# DIDV_-_Baixa_Latencia_Conex_o_Servos.net
KiCad netlist of a schematic drawn in EAGLE
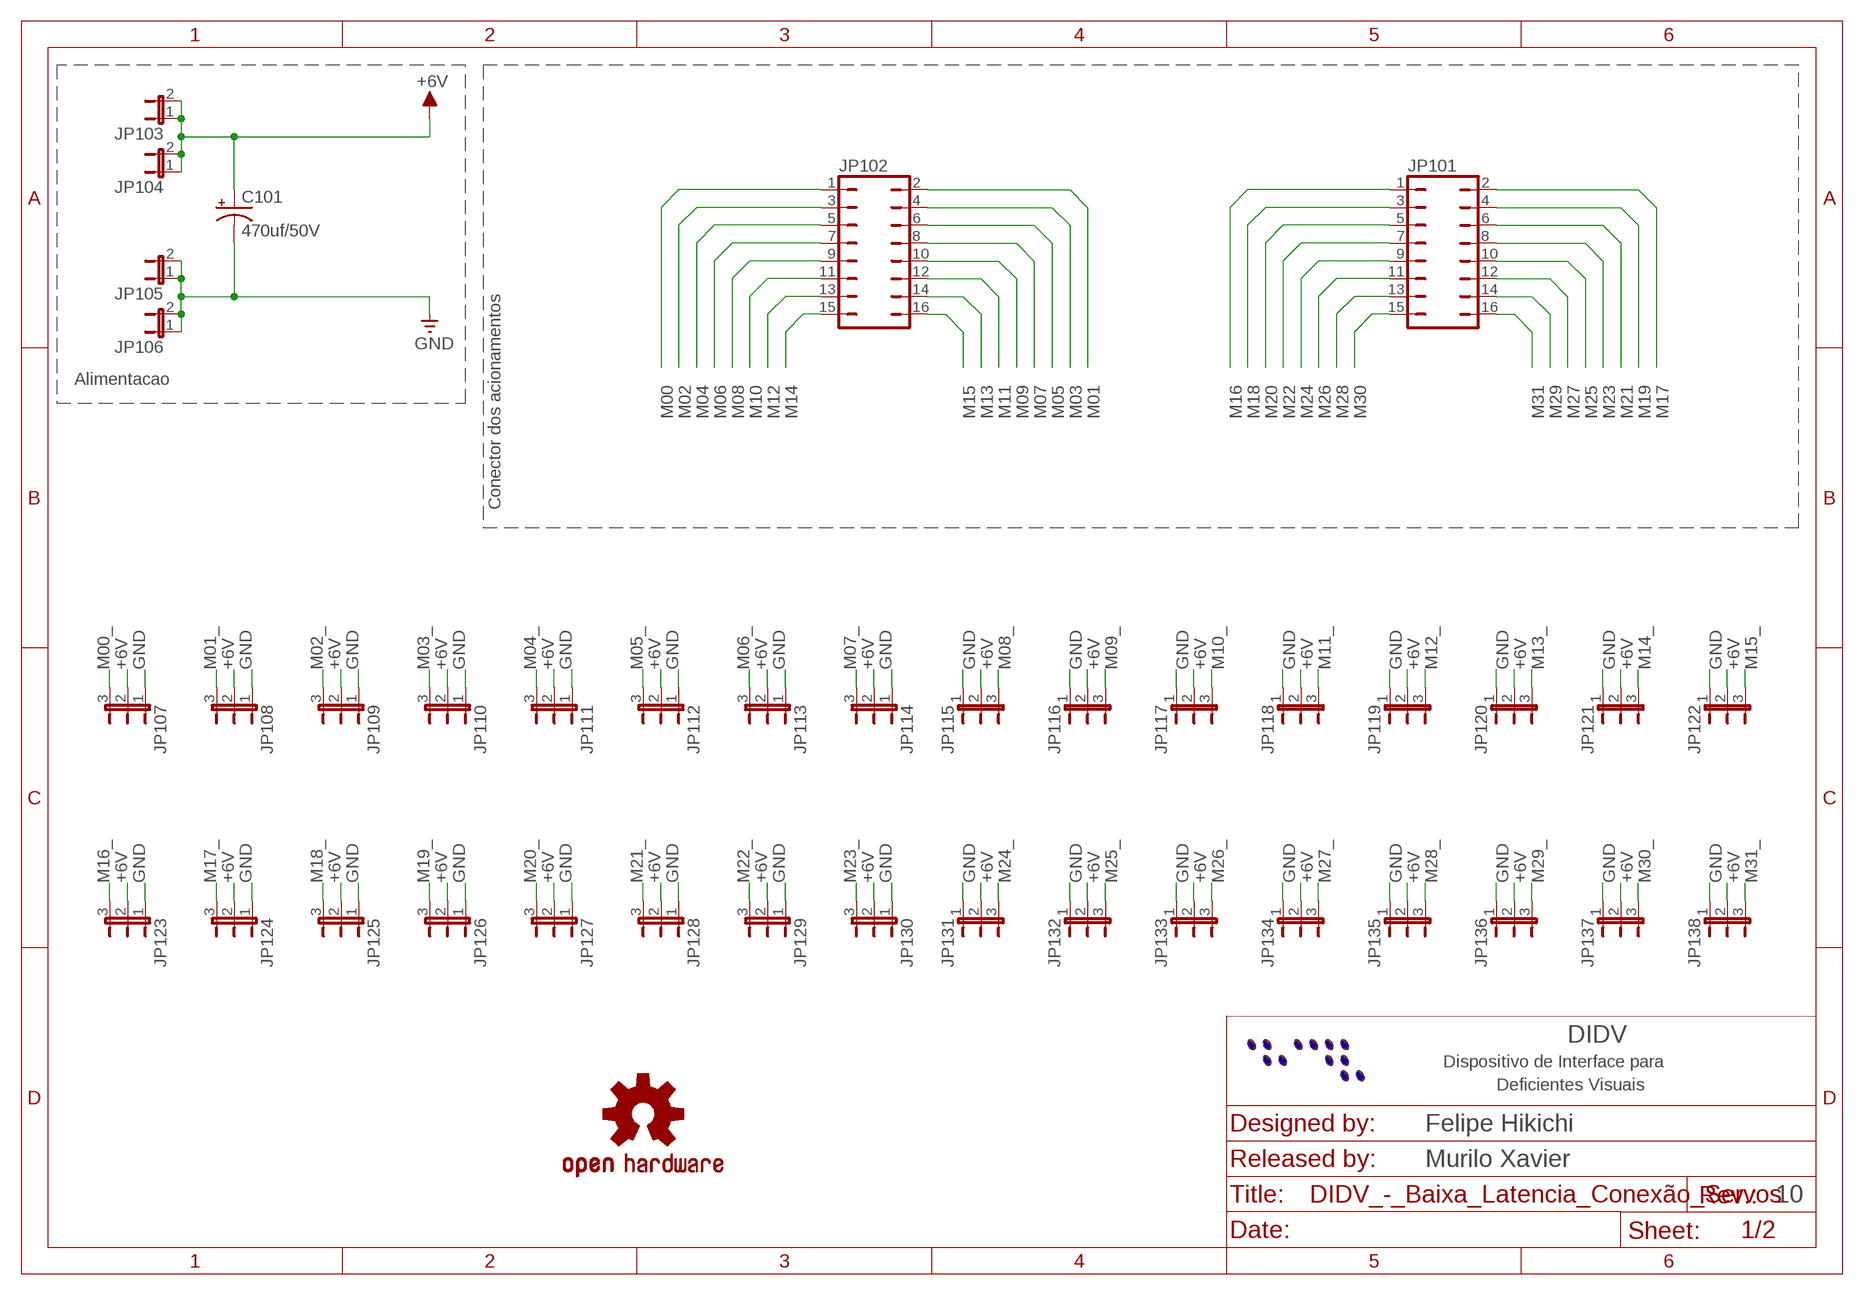
[diagram p0: schematic, sheet 1]
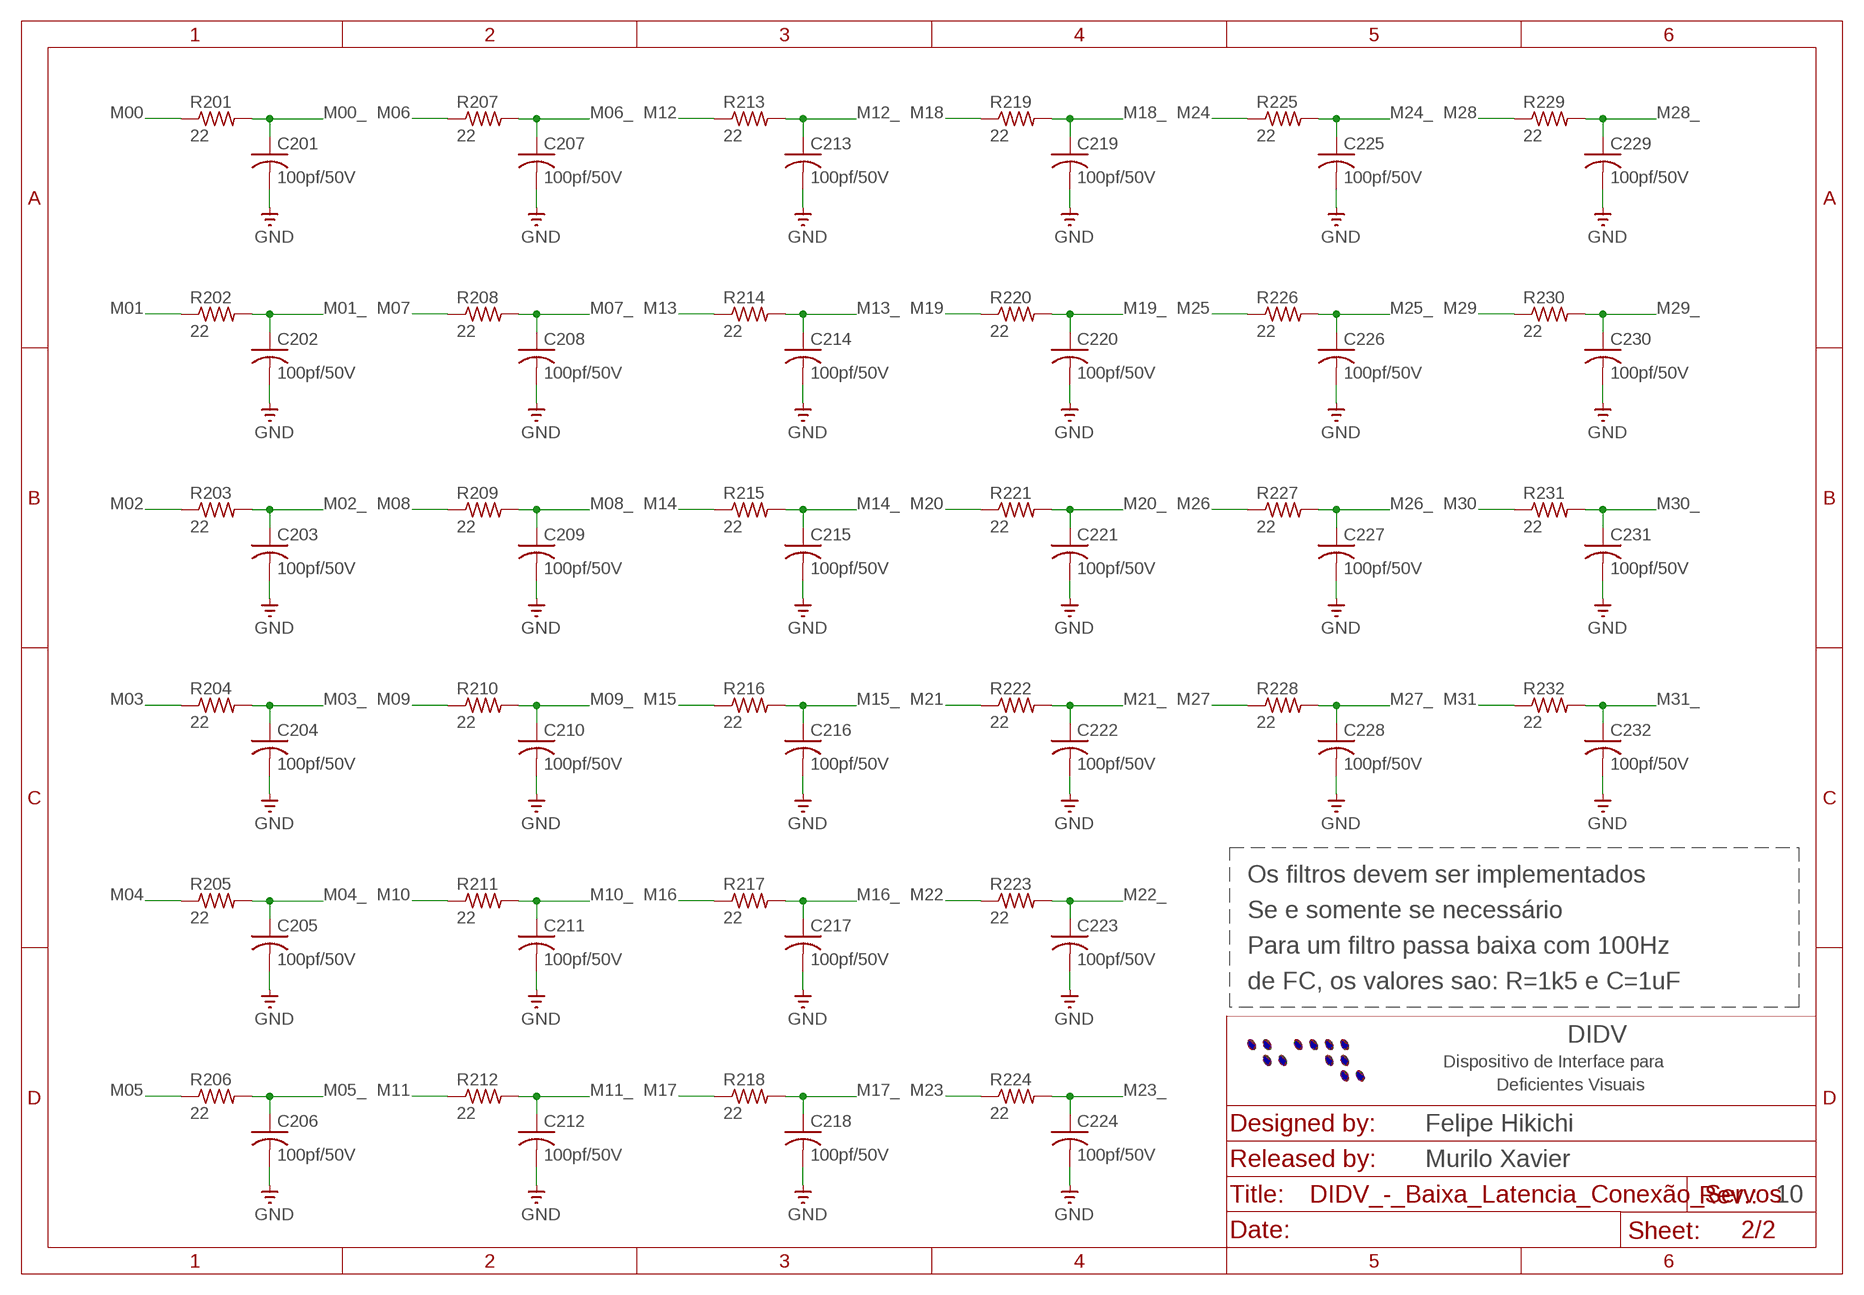
[diagram p1: schematic, sheet 2]

(export (version "E")
  (design (tool "Eeschema 10.0.6"))
  (components
    (comp (ref "C101")
      (value "470uf/50V")
      (footprint "eagle-import:140CLH-1010")
      (libsource (lib "eagle-import") (part "CPOL-US140CLH-1010"))
    )
    (comp (ref "JP101")
      (value "JP8Q")
      (footprint "eagle-import:JP8Q")
      (libsource (lib "eagle-import") (part "JP8Q"))
    )
    (comp (ref "JP102")
      (value "JP8Q")
      (footprint "eagle-import:JP8Q")
      (libsource (lib "eagle-import") (part "JP8Q"))
    )
    (comp (ref "JP103")
      (value "JP1E")
      (footprint "eagle-import:JP1")
      (libsource (lib "eagle-import") (part "JP1E"))
    )
    (comp (ref "JP104")
      (value "JP1E")
      (footprint "eagle-import:JP1")
      (libsource (lib "eagle-import") (part "JP1E"))
    )
    (comp (ref "JP105")
      (value "JP1E")
      (footprint "eagle-import:JP1")
      (libsource (lib "eagle-import") (part "JP1E"))
    )
    (comp (ref "JP106")
      (value "JP1E")
      (footprint "eagle-import:JP1")
      (libsource (lib "eagle-import") (part "JP1E"))
    )
    (comp (ref "JP107")
      (value "JP2E")
      (footprint "eagle-import:JP2")
      (libsource (lib "eagle-import") (part "JP2E"))
    )
    (comp (ref "JP108")
      (value "JP2E")
      (footprint "eagle-import:JP2")
      (libsource (lib "eagle-import") (part "JP2E"))
    )
    (comp (ref "JP109")
      (value "JP2E")
      (footprint "eagle-import:JP2")
      (libsource (lib "eagle-import") (part "JP2E"))
    )
    (comp (ref "JP110")
      (value "JP2E")
      (footprint "eagle-import:JP2")
      (libsource (lib "eagle-import") (part "JP2E"))
    )
    (comp (ref "JP111")
      (value "JP2E")
      (footprint "eagle-import:JP2")
      (libsource (lib "eagle-import") (part "JP2E"))
    )
    (comp (ref "JP112")
      (value "JP2E")
      (footprint "eagle-import:JP2")
      (libsource (lib "eagle-import") (part "JP2E"))
    )
    (comp (ref "JP113")
      (value "JP2E")
      (footprint "eagle-import:JP2")
      (libsource (lib "eagle-import") (part "JP2E"))
    )
    (comp (ref "JP114")
      (value "JP2E")
      (footprint "eagle-import:JP2")
      (libsource (lib "eagle-import") (part "JP2E"))
    )
    (comp (ref "JP115")
      (value "JP2E")
      (footprint "eagle-import:JP2")
      (libsource (lib "eagle-import") (part "JP2E"))
    )
    (comp (ref "JP116")
      (value "JP2E")
      (footprint "eagle-import:JP2")
      (libsource (lib "eagle-import") (part "JP2E"))
    )
    (comp (ref "JP117")
      (value "JP2E")
      (footprint "eagle-import:JP2")
      (libsource (lib "eagle-import") (part "JP2E"))
    )
    (comp (ref "JP118")
      (value "JP2E")
      (footprint "eagle-import:JP2")
      (libsource (lib "eagle-import") (part "JP2E"))
    )
    (comp (ref "JP119")
      (value "JP2E")
      (footprint "eagle-import:JP2")
      (libsource (lib "eagle-import") (part "JP2E"))
    )
    (comp (ref "JP120")
      (value "JP2E")
      (footprint "eagle-import:JP2")
      (libsource (lib "eagle-import") (part "JP2E"))
    )
    (comp (ref "JP121")
      (value "JP2E")
      (footprint "eagle-import:JP2")
      (libsource (lib "eagle-import") (part "JP2E"))
    )
    (comp (ref "JP122")
      (value "JP2E")
      (footprint "eagle-import:JP2")
      (libsource (lib "eagle-import") (part "JP2E"))
    )
    (comp (ref "JP123")
      (value "JP2E")
      (footprint "eagle-import:JP2")
      (libsource (lib "eagle-import") (part "JP2E"))
    )
    (comp (ref "JP124")
      (value "JP2E")
      (footprint "eagle-import:JP2")
      (libsource (lib "eagle-import") (part "JP2E"))
    )
    (comp (ref "JP125")
      (value "JP2E")
      (footprint "eagle-import:JP2")
      (libsource (lib "eagle-import") (part "JP2E"))
    )
    (comp (ref "JP126")
      (value "JP2E")
      (footprint "eagle-import:JP2")
      (libsource (lib "eagle-import") (part "JP2E"))
    )
    (comp (ref "JP127")
      (value "JP2E")
      (footprint "eagle-import:JP2")
      (libsource (lib "eagle-import") (part "JP2E"))
    )
    (comp (ref "JP128")
      (value "JP2E")
      (footprint "eagle-import:JP2")
      (libsource (lib "eagle-import") (part "JP2E"))
    )
    (comp (ref "JP129")
      (value "JP2E")
      (footprint "eagle-import:JP2")
      (libsource (lib "eagle-import") (part "JP2E"))
    )
    (comp (ref "JP130")
      (value "JP2E")
      (footprint "eagle-import:JP2")
      (libsource (lib "eagle-import") (part "JP2E"))
    )
    (comp (ref "JP131")
      (value "JP2E")
      (footprint "eagle-import:JP2")
      (libsource (lib "eagle-import") (part "JP2E"))
    )
    (comp (ref "JP132")
      (value "JP2E")
      (footprint "eagle-import:JP2")
      (libsource (lib "eagle-import") (part "JP2E"))
    )
    (comp (ref "JP133")
      (value "JP2E")
      (footprint "eagle-import:JP2")
      (libsource (lib "eagle-import") (part "JP2E"))
    )
    (comp (ref "JP134")
      (value "JP2E")
      (footprint "eagle-import:JP2")
      (libsource (lib "eagle-import") (part "JP2E"))
    )
    (comp (ref "JP135")
      (value "JP2E")
      (footprint "eagle-import:JP2")
      (libsource (lib "eagle-import") (part "JP2E"))
    )
    (comp (ref "JP136")
      (value "JP2E")
      (footprint "eagle-import:JP2")
      (libsource (lib "eagle-import") (part "JP2E"))
    )
    (comp (ref "JP137")
      (value "JP2E")
      (footprint "eagle-import:JP2")
      (libsource (lib "eagle-import") (part "JP2E"))
    )
    (comp (ref "JP138")
      (value "JP2E")
      (footprint "eagle-import:JP2")
      (libsource (lib "eagle-import") (part "JP2E"))
    )
    (comp (ref "LOGO101")
      (value "OSHW-LOGOL")
      (footprint "eagle-import:OSHW-LOGO-L")
      (libsource (lib "eagle-import") (part "OSHW-LOGOL"))
    )
    (comp (ref "C201")
      (value "100pf/50V")
      (footprint "eagle-import:C0603")
      (libsource (lib "eagle-import") (part "C-USC0603"))
    )
    (comp (ref "C202")
      (value "100pf/50V")
      (footprint "eagle-import:C0603")
      (libsource (lib "eagle-import") (part "C-USC0603"))
    )
    (comp (ref "C203")
      (value "100pf/50V")
      (footprint "eagle-import:C0603")
      (libsource (lib "eagle-import") (part "C-USC0603"))
    )
    (comp (ref "C204")
      (value "100pf/50V")
      (footprint "eagle-import:C0603")
      (libsource (lib "eagle-import") (part "C-USC0603"))
    )
    (comp (ref "C205")
      (value "100pf/50V")
      (footprint "eagle-import:C0603")
      (libsource (lib "eagle-import") (part "C-USC0603"))
    )
    (comp (ref "C206")
      (value "100pf/50V")
      (footprint "eagle-import:C0603")
      (libsource (lib "eagle-import") (part "C-USC0603"))
    )
    (comp (ref "C207")
      (value "100pf/50V")
      (footprint "eagle-import:C0603")
      (libsource (lib "eagle-import") (part "C-USC0603"))
    )
    (comp (ref "C208")
      (value "100pf/50V")
      (footprint "eagle-import:C0603")
      (libsource (lib "eagle-import") (part "C-USC0603"))
    )
    (comp (ref "C209")
      (value "100pf/50V")
      (footprint "eagle-import:C0603")
      (libsource (lib "eagle-import") (part "C-USC0603"))
    )
    (comp (ref "C210")
      (value "100pf/50V")
      (footprint "eagle-import:C0603")
      (libsource (lib "eagle-import") (part "C-USC0603"))
    )
    (comp (ref "C211")
      (value "100pf/50V")
      (footprint "eagle-import:C0603")
      (libsource (lib "eagle-import") (part "C-USC0603"))
    )
    (comp (ref "C212")
      (value "100pf/50V")
      (footprint "eagle-import:C0603")
      (libsource (lib "eagle-import") (part "C-USC0603"))
    )
    (comp (ref "C213")
      (value "100pf/50V")
      (footprint "eagle-import:C0603")
      (libsource (lib "eagle-import") (part "C-USC0603"))
    )
    (comp (ref "C214")
      (value "100pf/50V")
      (footprint "eagle-import:C0603")
      (libsource (lib "eagle-import") (part "C-USC0603"))
    )
    (comp (ref "C215")
      (value "100pf/50V")
      (footprint "eagle-import:C0603")
      (libsource (lib "eagle-import") (part "C-USC0603"))
    )
    (comp (ref "C216")
      (value "100pf/50V")
      (footprint "eagle-import:C0603")
      (libsource (lib "eagle-import") (part "C-USC0603"))
    )
    (comp (ref "C217")
      (value "100pf/50V")
      (footprint "eagle-import:C0603")
      (libsource (lib "eagle-import") (part "C-USC0603"))
    )
    (comp (ref "C218")
      (value "100pf/50V")
      (footprint "eagle-import:C0603")
      (libsource (lib "eagle-import") (part "C-USC0603"))
    )
    (comp (ref "C219")
      (value "100pf/50V")
      (footprint "eagle-import:C0603")
      (libsource (lib "eagle-import") (part "C-USC0603"))
    )
    (comp (ref "C220")
      (value "100pf/50V")
      (footprint "eagle-import:C0603")
      (libsource (lib "eagle-import") (part "C-USC0603"))
    )
    (comp (ref "C221")
      (value "100pf/50V")
      (footprint "eagle-import:C0603")
      (libsource (lib "eagle-import") (part "C-USC0603"))
    )
    (comp (ref "C222")
      (value "100pf/50V")
      (footprint "eagle-import:C0603")
      (libsource (lib "eagle-import") (part "C-USC0603"))
    )
    (comp (ref "C223")
      (value "100pf/50V")
      (footprint "eagle-import:C0603")
      (libsource (lib "eagle-import") (part "C-USC0603"))
    )
    (comp (ref "C224")
      (value "100pf/50V")
      (footprint "eagle-import:C0603")
      (libsource (lib "eagle-import") (part "C-USC0603"))
    )
    (comp (ref "C225")
      (value "100pf/50V")
      (footprint "eagle-import:C0603")
      (libsource (lib "eagle-import") (part "C-USC0603"))
    )
    (comp (ref "C226")
      (value "100pf/50V")
      (footprint "eagle-import:C0603")
      (libsource (lib "eagle-import") (part "C-USC0603"))
    )
    (comp (ref "C227")
      (value "100pf/50V")
      (footprint "eagle-import:C0603")
      (libsource (lib "eagle-import") (part "C-USC0603"))
    )
    (comp (ref "C228")
      (value "100pf/50V")
      (footprint "eagle-import:C0603")
      (libsource (lib "eagle-import") (part "C-USC0603"))
    )
    (comp (ref "C229")
      (value "100pf/50V")
      (footprint "eagle-import:C0603")
      (libsource (lib "eagle-import") (part "C-USC0603"))
    )
    (comp (ref "C230")
      (value "100pf/50V")
      (footprint "eagle-import:C0603")
      (libsource (lib "eagle-import") (part "C-USC0603"))
    )
    (comp (ref "C231")
      (value "100pf/50V")
      (footprint "eagle-import:C0603")
      (libsource (lib "eagle-import") (part "C-USC0603"))
    )
    (comp (ref "C232")
      (value "100pf/50V")
      (footprint "eagle-import:C0603")
      (libsource (lib "eagle-import") (part "C-USC0603"))
    )
    (comp (ref "R201")
      (value "22")
      (footprint "eagle-import:R0603")
      (libsource (lib "eagle-import") (part "R-US_R0603"))
    )
    (comp (ref "R202")
      (value "22")
      (footprint "eagle-import:R0603")
      (libsource (lib "eagle-import") (part "R-US_R0603"))
    )
    (comp (ref "R203")
      (value "22")
      (footprint "eagle-import:R0603")
      (libsource (lib "eagle-import") (part "R-US_R0603"))
    )
    (comp (ref "R204")
      (value "22")
      (footprint "eagle-import:R0603")
      (libsource (lib "eagle-import") (part "R-US_R0603"))
    )
    (comp (ref "R205")
      (value "22")
      (footprint "eagle-import:R0603")
      (libsource (lib "eagle-import") (part "R-US_R0603"))
    )
    (comp (ref "R206")
      (value "22")
      (footprint "eagle-import:R0603")
      (libsource (lib "eagle-import") (part "R-US_R0603"))
    )
    (comp (ref "R207")
      (value "22")
      (footprint "eagle-import:R0603")
      (libsource (lib "eagle-import") (part "R-US_R0603"))
    )
    (comp (ref "R208")
      (value "22")
      (footprint "eagle-import:R0603")
      (libsource (lib "eagle-import") (part "R-US_R0603"))
    )
    (comp (ref "R209")
      (value "22")
      (footprint "eagle-import:R0603")
      (libsource (lib "eagle-import") (part "R-US_R0603"))
    )
    (comp (ref "R210")
      (value "22")
      (footprint "eagle-import:R0603")
      (libsource (lib "eagle-import") (part "R-US_R0603"))
    )
    (comp (ref "R211")
      (value "22")
      (footprint "eagle-import:R0603")
      (libsource (lib "eagle-import") (part "R-US_R0603"))
    )
    (comp (ref "R212")
      (value "22")
      (footprint "eagle-import:R0603")
      (libsource (lib "eagle-import") (part "R-US_R0603"))
    )
    (comp (ref "R213")
      (value "22")
      (footprint "eagle-import:R0603")
      (libsource (lib "eagle-import") (part "R-US_R0603"))
    )
    (comp (ref "R214")
      (value "22")
      (footprint "eagle-import:R0603")
      (libsource (lib "eagle-import") (part "R-US_R0603"))
    )
    (comp (ref "R215")
      (value "22")
      (footprint "eagle-import:R0603")
      (libsource (lib "eagle-import") (part "R-US_R0603"))
    )
    (comp (ref "R216")
      (value "22")
      (footprint "eagle-import:R0603")
      (libsource (lib "eagle-import") (part "R-US_R0603"))
    )
    (comp (ref "R217")
      (value "22")
      (footprint "eagle-import:R0603")
      (libsource (lib "eagle-import") (part "R-US_R0603"))
    )
    (comp (ref "R218")
      (value "22")
      (footprint "eagle-import:R0603")
      (libsource (lib "eagle-import") (part "R-US_R0603"))
    )
    (comp (ref "R219")
      (value "22")
      (footprint "eagle-import:R0603")
      (libsource (lib "eagle-import") (part "R-US_R0603"))
    )
    (comp (ref "R220")
      (value "22")
      (footprint "eagle-import:R0603")
      (libsource (lib "eagle-import") (part "R-US_R0603"))
    )
    (comp (ref "R221")
      (value "22")
      (footprint "eagle-import:R0603")
      (libsource (lib "eagle-import") (part "R-US_R0603"))
    )
    (comp (ref "R222")
      (value "22")
      (footprint "eagle-import:R0603")
      (libsource (lib "eagle-import") (part "R-US_R0603"))
    )
    (comp (ref "R223")
      (value "22")
      (footprint "eagle-import:R0603")
      (libsource (lib "eagle-import") (part "R-US_R0603"))
    )
    (comp (ref "R224")
      (value "22")
      (footprint "eagle-import:R0603")
      (libsource (lib "eagle-import") (part "R-US_R0603"))
    )
    (comp (ref "R225")
      (value "22")
      (footprint "eagle-import:R0603")
      (libsource (lib "eagle-import") (part "R-US_R0603"))
    )
    (comp (ref "R226")
      (value "22")
      (footprint "eagle-import:R0603")
      (libsource (lib "eagle-import") (part "R-US_R0603"))
    )
    (comp (ref "R227")
      (value "22")
      (footprint "eagle-import:R0603")
      (libsource (lib "eagle-import") (part "R-US_R0603"))
    )
    (comp (ref "R228")
      (value "22")
      (footprint "eagle-import:R0603")
      (libsource (lib "eagle-import") (part "R-US_R0603"))
    )
    (comp (ref "R229")
      (value "22")
      (footprint "eagle-import:R0603")
      (libsource (lib "eagle-import") (part "R-US_R0603"))
    )
    (comp (ref "R230")
      (value "22")
      (footprint "eagle-import:R0603")
      (libsource (lib "eagle-import") (part "R-US_R0603"))
    )
    (comp (ref "R231")
      (value "22")
      (footprint "eagle-import:R0603")
      (libsource (lib "eagle-import") (part "R-US_R0603"))
    )
    (comp (ref "R232")
      (value "22")
      (footprint "eagle-import:R0603")
      (libsource (lib "eagle-import") (part "R-US_R0603"))
    )
  )
  (nets
    (net (code "1") (name "+6V") (class "Default")
      (node (ref "C101") (pin "+") (pinfunction "+_+") (pintype "passive"))
      (node (ref "JP103") (pin "1") (pinfunction "1_1") (pintype "passive"))
      (node (ref "JP103") (pin "2") (pinfunction "2_2") (pintype "passive"))
      (node (ref "JP104") (pin "1") (pinfunction "1_1") (pintype "passive"))
      (node (ref "JP104") (pin "2") (pinfunction "2_2") (pintype "passive"))
      (node (ref "JP107") (pin "2") (pinfunction "2_2") (pintype "passive"))
      (node (ref "JP108") (pin "2") (pinfunction "2_2") (pintype "passive"))
      (node (ref "JP109") (pin "2") (pinfunction "2_2") (pintype "passive"))
      (node (ref "JP110") (pin "2") (pinfunction "2_2") (pintype "passive"))
      (node (ref "JP111") (pin "2") (pinfunction "2_2") (pintype "passive"))
      (node (ref "JP112") (pin "2") (pinfunction "2_2") (pintype "passive"))
      (node (ref "JP113") (pin "2") (pinfunction "2_2") (pintype "passive"))
      (node (ref "JP114") (pin "2") (pinfunction "2_2") (pintype "passive"))
      (node (ref "JP115") (pin "2") (pinfunction "2_2") (pintype "passive"))
      (node (ref "JP116") (pin "2") (pinfunction "2_2") (pintype "passive"))
      (node (ref "JP117") (pin "2") (pinfunction "2_2") (pintype "passive"))
      (node (ref "JP118") (pin "2") (pinfunction "2_2") (pintype "passive"))
      (node (ref "JP119") (pin "2") (pinfunction "2_2") (pintype "passive"))
      (node (ref "JP120") (pin "2") (pinfunction "2_2") (pintype "passive"))
      (node (ref "JP121") (pin "2") (pinfunction "2_2") (pintype "passive"))
      (node (ref "JP122") (pin "2") (pinfunction "2_2") (pintype "passive"))
      (node (ref "JP123") (pin "2") (pinfunction "2_2") (pintype "passive"))
      (node (ref "JP124") (pin "2") (pinfunction "2_2") (pintype "passive"))
      (node (ref "JP125") (pin "2") (pinfunction "2_2") (pintype "passive"))
      (node (ref "JP126") (pin "2") (pinfunction "2_2") (pintype "passive"))
      (node (ref "JP127") (pin "2") (pinfunction "2_2") (pintype "passive"))
      (node (ref "JP128") (pin "2") (pinfunction "2_2") (pintype "passive"))
      (node (ref "JP129") (pin "2") (pinfunction "2_2") (pintype "passive"))
      (node (ref "JP130") (pin "2") (pinfunction "2_2") (pintype "passive"))
      (node (ref "JP131") (pin "2") (pinfunction "2_2") (pintype "passive"))
      (node (ref "JP132") (pin "2") (pinfunction "2_2") (pintype "passive"))
      (node (ref "JP133") (pin "2") (pinfunction "2_2") (pintype "passive"))
      (node (ref "JP134") (pin "2") (pinfunction "2_2") (pintype "passive"))
      (node (ref "JP135") (pin "2") (pinfunction "2_2") (pintype "passive"))
      (node (ref "JP136") (pin "2") (pinfunction "2_2") (pintype "passive"))
      (node (ref "JP137") (pin "2") (pinfunction "2_2") (pintype "passive"))
      (node (ref "JP138") (pin "2") (pinfunction "2_2") (pintype "passive"))
    )
    (net (code "2") (name "GND") (class "Default")
      (node (ref "C101") (pin "-") (pinfunction "-_-") (pintype "passive"))
      (node (ref "C201") (pin "2") (pinfunction "2_2") (pintype "passive"))
      (node (ref "C202") (pin "2") (pinfunction "2_2") (pintype "passive"))
      (node (ref "C203") (pin "2") (pinfunction "2_2") (pintype "passive"))
      (node (ref "C204") (pin "2") (pinfunction "2_2") (pintype "passive"))
      (node (ref "C205") (pin "2") (pinfunction "2_2") (pintype "passive"))
      (node (ref "C206") (pin "2") (pinfunction "2_2") (pintype "passive"))
      (node (ref "C207") (pin "2") (pinfunction "2_2") (pintype "passive"))
      (node (ref "C208") (pin "2") (pinfunction "2_2") (pintype "passive"))
      (node (ref "C209") (pin "2") (pinfunction "2_2") (pintype "passive"))
      (node (ref "C210") (pin "2") (pinfunction "2_2") (pintype "passive"))
      (node (ref "C211") (pin "2") (pinfunction "2_2") (pintype "passive"))
      (node (ref "C212") (pin "2") (pinfunction "2_2") (pintype "passive"))
      (node (ref "C213") (pin "2") (pinfunction "2_2") (pintype "passive"))
      (node (ref "C214") (pin "2") (pinfunction "2_2") (pintype "passive"))
      (node (ref "C215") (pin "2") (pinfunction "2_2") (pintype "passive"))
      (node (ref "C216") (pin "2") (pinfunction "2_2") (pintype "passive"))
      (node (ref "C217") (pin "2") (pinfunction "2_2") (pintype "passive"))
      (node (ref "C218") (pin "2") (pinfunction "2_2") (pintype "passive"))
      (node (ref "C219") (pin "2") (pinfunction "2_2") (pintype "passive"))
      (node (ref "C220") (pin "2") (pinfunction "2_2") (pintype "passive"))
      (node (ref "C221") (pin "2") (pinfunction "2_2") (pintype "passive"))
      (node (ref "C222") (pin "2") (pinfunction "2_2") (pintype "passive"))
      (node (ref "C223") (pin "2") (pinfunction "2_2") (pintype "passive"))
      (node (ref "C224") (pin "2") (pinfunction "2_2") (pintype "passive"))
      (node (ref "C225") (pin "2") (pinfunction "2_2") (pintype "passive"))
      (node (ref "C226") (pin "2") (pinfunction "2_2") (pintype "passive"))
      (node (ref "C227") (pin "2") (pinfunction "2_2") (pintype "passive"))
      (node (ref "C228") (pin "2") (pinfunction "2_2") (pintype "passive"))
      (node (ref "C229") (pin "2") (pinfunction "2_2") (pintype "passive"))
      (node (ref "C230") (pin "2") (pinfunction "2_2") (pintype "passive"))
      (node (ref "C231") (pin "2") (pinfunction "2_2") (pintype "passive"))
      (node (ref "C232") (pin "2") (pinfunction "2_2") (pintype "passive"))
      (node (ref "JP105") (pin "1") (pinfunction "1_1") (pintype "passive"))
      (node (ref "JP105") (pin "2") (pinfunction "2_2") (pintype "passive"))
      (node (ref "JP106") (pin "1") (pinfunction "1_1") (pintype "passive"))
      (node (ref "JP106") (pin "2") (pinfunction "2_2") (pintype "passive"))
      (node (ref "JP107") (pin "1") (pinfunction "1_1") (pintype "passive"))
      (node (ref "JP108") (pin "1") (pinfunction "1_1") (pintype "passive"))
      (node (ref "JP109") (pin "1") (pinfunction "1_1") (pintype "passive"))
      (node (ref "JP110") (pin "1") (pinfunction "1_1") (pintype "passive"))
      (node (ref "JP111") (pin "1") (pinfunction "1_1") (pintype "passive"))
      (node (ref "JP112") (pin "1") (pinfunction "1_1") (pintype "passive"))
      (node (ref "JP113") (pin "1") (pinfunction "1_1") (pintype "passive"))
      (node (ref "JP114") (pin "1") (pinfunction "1_1") (pintype "passive"))
      (node (ref "JP115") (pin "1") (pinfunction "1_1") (pintype "passive"))
      (node (ref "JP116") (pin "1") (pinfunction "1_1") (pintype "passive"))
      (node (ref "JP117") (pin "1") (pinfunction "1_1") (pintype "passive"))
      (node (ref "JP118") (pin "1") (pinfunction "1_1") (pintype "passive"))
      (node (ref "JP119") (pin "1") (pinfunction "1_1") (pintype "passive"))
      (node (ref "JP120") (pin "1") (pinfunction "1_1") (pintype "passive"))
      (node (ref "JP121") (pin "1") (pinfunction "1_1") (pintype "passive"))
      (node (ref "JP122") (pin "1") (pinfunction "1_1") (pintype "passive"))
      (node (ref "JP123") (pin "1") (pinfunction "1_1") (pintype "passive"))
      (node (ref "JP124") (pin "1") (pinfunction "1_1") (pintype "passive"))
      (node (ref "JP125") (pin "1") (pinfunction "1_1") (pintype "passive"))
      (node (ref "JP126") (pin "1") (pinfunction "1_1") (pintype "passive"))
      (node (ref "JP127") (pin "1") (pinfunction "1_1") (pintype "passive"))
      (node (ref "JP128") (pin "1") (pinfunction "1_1") (pintype "passive"))
      (node (ref "JP129") (pin "1") (pinfunction "1_1") (pintype "passive"))
      (node (ref "JP130") (pin "1") (pinfunction "1_1") (pintype "passive"))
      (node (ref "JP131") (pin "1") (pinfunction "1_1") (pintype "passive"))
      (node (ref "JP132") (pin "1") (pinfunction "1_1") (pintype "passive"))
      (node (ref "JP133") (pin "1") (pinfunction "1_1") (pintype "passive"))
      (node (ref "JP134") (pin "1") (pinfunction "1_1") (pintype "passive"))
      (node (ref "JP135") (pin "1") (pinfunction "1_1") (pintype "passive"))
      (node (ref "JP136") (pin "1") (pinfunction "1_1") (pintype "passive"))
      (node (ref "JP137") (pin "1") (pinfunction "1_1") (pintype "passive"))
      (node (ref "JP138") (pin "1") (pinfunction "1_1") (pintype "passive"))
    )
    (net (code "3") (name "M00") (class "Default")
      (node (ref "JP102") (pin "1") (pinfunction "1_1") (pintype "passive"))
      (node (ref "R201") (pin "1") (pinfunction "1_1") (pintype "passive"))
    )
    (net (code "4") (name "M00_") (class "Default")
      (node (ref "C201") (pin "1") (pinfunction "1_1") (pintype "passive"))
      (node (ref "JP107") (pin "3") (pinfunction "3_3") (pintype "passive"))
      (node (ref "R201") (pin "2") (pinfunction "2_2") (pintype "passive"))
    )
    (net (code "5") (name "M01") (class "Default")
      (node (ref "JP102") (pin "2") (pinfunction "2_2") (pintype "passive"))
      (node (ref "R202") (pin "1") (pinfunction "1_1") (pintype "passive"))
    )
    (net (code "6") (name "M01_") (class "Default")
      (node (ref "C202") (pin "1") (pinfunction "1_1") (pintype "passive"))
      (node (ref "JP108") (pin "3") (pinfunction "3_3") (pintype "passive"))
      (node (ref "R202") (pin "2") (pinfunction "2_2") (pintype "passive"))
    )
    (net (code "7") (name "M02") (class "Default")
      (node (ref "JP102") (pin "3") (pinfunction "3_3") (pintype "passive"))
      (node (ref "R203") (pin "1") (pinfunction "1_1") (pintype "passive"))
    )
    (net (code "8") (name "M02_") (class "Default")
      (node (ref "C203") (pin "1") (pinfunction "1_1") (pintype "passive"))
      (node (ref "JP109") (pin "3") (pinfunction "3_3") (pintype "passive"))
      (node (ref "R203") (pin "2") (pinfunction "2_2") (pintype "passive"))
    )
    (net (code "9") (name "M03") (class "Default")
      (node (ref "JP102") (pin "4") (pinfunction "4_4") (pintype "passive"))
      (node (ref "R204") (pin "1") (pinfunction "1_1") (pintype "passive"))
    )
    (net (code "10") (name "M03_") (class "Default")
      (node (ref "C204") (pin "1") (pinfunction "1_1") (pintype "passive"))
      (node (ref "JP110") (pin "3") (pinfunction "3_3") (pintype "passive"))
      (node (ref "R204") (pin "2") (pinfunction "2_2") (pintype "passive"))
    )
    (net (code "11") (name "M04") (class "Default")
      (node (ref "JP102") (pin "5") (pinfunction "5_5") (pintype "passive"))
      (node (ref "R205") (pin "1") (pinfunction "1_1") (pintype "passive"))
    )
    (net (code "12") (name "M04_") (class "Default")
      (node (ref "C205") (pin "1") (pinfunction "1_1") (pintype "passive"))
      (node (ref "JP111") (pin "3") (pinfunction "3_3") (pintype "passive"))
      (node (ref "R205") (pin "2") (pinfunction "2_2") (pintype "passive"))
    )
    (net (code "13") (name "M05") (class "Default")
      (node (ref "JP102") (pin "6") (pinfunction "6_6") (pintype "passive"))
      (node (ref "R206") (pin "1") (pinfunction "1_1") (pintype "passive"))
    )
    (net (code "14") (name "M05_") (class "Default")
      (node (ref "C206") (pin "1") (pinfunction "1_1") (pintype "passive"))
      (node (ref "JP112") (pin "3") (pinfunction "3_3") (pintype "passive"))
      (node (ref "R206") (pin "2") (pinfunction "2_2") (pintype "passive"))
    )
    (net (code "15") (name "M06") (class "Default")
      (node (ref "JP102") (pin "7") (pinfunction "7_7") (pintype "passive"))
      (node (ref "R207") (pin "1") (pinfunction "1_1") (pintype "passive"))
    )
    (net (code "16") (name "M06_") (class "Default")
      (node (ref "C207") (pin "1") (pinfunction "1_1") (pintype "passive"))
      (node (ref "JP113") (pin "3") (pinfunction "3_3") (pintype "passive"))
      (node (ref "R207") (pin "2") (pinfunction "2_2") (pintype "passive"))
    )
    (net (code "17") (name "M07") (class "Default")
      (node (ref "JP102") (pin "8") (pinfunction "8_8") (pintype "passive"))
      (node (ref "R208") (pin "1") (pinfunction "1_1") (pintype "passive"))
    )
    (net (code "18") (name "M07_") (class "Default")
      (node (ref "C208") (pin "1") (pinfunction "1_1") (pintype "passive"))
      (node (ref "JP114") (pin "3") (pinfunction "3_3") (pintype "passive"))
      (node (ref "R208") (pin "2") (pinfunction "2_2") (pintype "passive"))
    )
    (net (code "19") (name "M08") (class "Default")
      (node (ref "JP102") (pin "9") (pinfunction "9_9") (pintype "passive"))
      (node (ref "R209") (pin "1") (pinfunction "1_1") (pintype "passive"))
    )
    (net (code "20") (name "M08_") (class "Default")
      (node (ref "C209") (pin "1") (pinfunction "1_1") (pintype "passive"))
      (node (ref "JP115") (pin "3") (pinfunction "3_3") (pintype "passive"))
      (node (ref "R209") (pin "2") (pinfunction "2_2") (pintype "passive"))
    )
    (net (code "21") (name "M09") (class "Default")
      (node (ref "JP102") (pin "10") (pinfunction "10_10") (pintype "passive"))
      (node (ref "R210") (pin "1") (pinfunction "1_1") (pintype "passive"))
    )
    (net (code "22") (name "M09_") (class "Default")
      (node (ref "C210") (pin "1") (pinfunction "1_1") (pintype "passive"))
      (node (ref "JP116") (pin "3") (pinfunction "3_3") (pintype "passive"))
      (node (ref "R210") (pin "2") (pinfunction "2_2") (pintype "passive"))
    )
    (net (code "23") (name "M10") (class "Default")
      (node (ref "JP102") (pin "11") (pinfunction "11_11") (pintype "passive"))
      (node (ref "R211") (pin "1") (pinfunction "1_1") (pintype "passive"))
    )
    (net (code "24") (name "M10_") (class "Default")
      (node (ref "C211") (pin "1") (pinfunction "1_1") (pintype "passive"))
      (node (ref "JP117") (pin "3") (pinfunction "3_3") (pintype "passive"))
      (node (ref "R211") (pin "2") (pinfunction "2_2") (pintype "passive"))
    )
    (net (code "25") (name "M11") (class "Default")
      (node (ref "JP102") (pin "12") (pinfunction "12_12") (pintype "passive"))
      (node (ref "R212") (pin "1") (pinfunction "1_1") (pintype "passive"))
    )
    (net (code "26") (name "M11_") (class "Default")
      (node (ref "C212") (pin "1") (pinfunction "1_1") (pintype "passive"))
      (node (ref "JP118") (pin "3") (pinfunction "3_3") (pintype "passive"))
      (node (ref "R212") (pin "2") (pinfunction "2_2") (pintype "passive"))
    )
    (net (code "27") (name "M12") (class "Default")
      (node (ref "JP102") (pin "13") (pinfunction "13_13") (pintype "passive"))
      (node (ref "R213") (pin "1") (pinfunction "1_1") (pintype "passive"))
    )
    (net (code "28") (name "M12_") (class "Default")
      (node (ref "C213") (pin "1") (pinfunction "1_1") (pintype "passive"))
      (node (ref "JP119") (pin "3") (pinfunction "3_3") (pintype "passive"))
      (node (ref "R213") (pin "2") (pinfunction "2_2") (pintype "passive"))
    )
    (net (code "29") (name "M13") (class "Default")
      (node (ref "JP102") (pin "14") (pinfunction "14_14") (pintype "passive"))
      (node (ref "R214") (pin "1") (pinfunction "1_1") (pintype "passive"))
    )
    (net (code "30") (name "M13_") (class "Default")
      (node (ref "C214") (pin "1") (pinfunction "1_1") (pintype "passive"))
      (node (ref "JP120") (pin "3") (pinfunction "3_3") (pintype "passive"))
      (node (ref "R214") (pin "2") (pinfunction "2_2") (pintype "passive"))
    )
    (net (code "31") (name "M14") (class "Default")
      (node (ref "JP102") (pin "15") (pinfunction "15_15") (pintype "passive"))
      (node (ref "R215") (pin "1") (pinfunction "1_1") (pintype "passive"))
    )
    (net (code "32") (name "M14_") (class "Default")
      (node (ref "C215") (pin "1") (pinfunction "1_1") (pintype "passive"))
      (node (ref "JP121") (pin "3") (pinfunction "3_3") (pintype "passive"))
      (node (ref "R215") (pin "2") (pinfunction "2_2") (pintype "passive"))
    )
    (net (code "33") (name "M15") (class "Default")
      (node (ref "JP102") (pin "16") (pinfunction "16_16") (pintype "passive"))
      (node (ref "R216") (pin "1") (pinfunction "1_1") (pintype "passive"))
    )
    (net (code "34") (name "M15_") (class "Default")
      (node (ref "C216") (pin "1") (pinfunction "1_1") (pintype "passive"))
      (node (ref "JP122") (pin "3") (pinfunction "3_3") (pintype "passive"))
      (node (ref "R216") (pin "2") (pinfunction "2_2") (pintype "passive"))
    )
    (net (code "35") (name "M16") (class "Default")
      (node (ref "JP101") (pin "1") (pinfunction "1_1") (pintype "passive"))
      (node (ref "R217") (pin "1") (pinfunction "1_1") (pintype "passive"))
    )
    (net (code "36") (name "M16_") (class "Default")
      (node (ref "C217") (pin "1") (pinfunction "1_1") (pintype "passive"))
      (node (ref "JP123") (pin "3") (pinfunction "3_3") (pintype "passive"))
      (node (ref "R217") (pin "2") (pinfunction "2_2") (pintype "passive"))
    )
    (net (code "37") (name "M17") (class "Default")
      (node (ref "JP101") (pin "2") (pinfunction "2_2") (pintype "passive"))
      (node (ref "R218") (pin "1") (pinfunction "1_1") (pintype "passive"))
    )
    (net (code "38") (name "M17_") (class "Default")
      (node (ref "C218") (pin "1") (pinfunction "1_1") (pintype "passive"))
      (node (ref "JP124") (pin "3") (pinfunction "3_3") (pintype "passive"))
      (node (ref "R218") (pin "2") (pinfunction "2_2") (pintype "passive"))
    )
    (net (code "39") (name "M18") (class "Default")
      (node (ref "JP101") (pin "3") (pinfunction "3_3") (pintype "passive"))
      (node (ref "R219") (pin "1") (pinfunction "1_1") (pintype "passive"))
    )
    (net (code "40") (name "M18_") (class "Default")
      (node (ref "C219") (pin "1") (pinfunction "1_1") (pintype "passive"))
      (node (ref "JP125") (pin "3") (pinfunction "3_3") (pintype "passive"))
      (node (ref "R219") (pin "2") (pinfunction "2_2") (pintype "passive"))
    )
    (net (code "41") (name "M19") (class "Default")
      (node (ref "JP101") (pin "4") (pinfunction "4_4") (pintype "passive"))
      (node (ref "R220") (pin "1") (pinfunction "1_1") (pintype "passive"))
    )
    (net (code "42") (name "M19_") (class "Default")
      (node (ref "C220") (pin "1") (pinfunction "1_1") (pintype "passive"))
      (node (ref "JP126") (pin "3") (pinfunction "3_3") (pintype "passive"))
      (node (ref "R220") (pin "2") (pinfunction "2_2") (pintype "passive"))
    )
    (net (code "43") (name "M20") (class "Default")
      (node (ref "JP101") (pin "5") (pinfunction "5_5") (pintype "passive"))
      (node (ref "R221") (pin "1") (pinfunction "1_1") (pintype "passive"))
    )
    (net (code "44") (name "M20_") (class "Default")
      (node (ref "C221") (pin "1") (pinfunction "1_1") (pintype "passive"))
      (node (ref "JP127") (pin "3") (pinfunction "3_3") (pintype "passive"))
      (node (ref "R221") (pin "2") (pinfunction "2_2") (pintype "passive"))
    )
    (net (code "45") (name "M21") (class "Default")
      (node (ref "JP101") (pin "6") (pinfunction "6_6") (pintype "passive"))
      (node (ref "R222") (pin "1") (pinfunction "1_1") (pintype "passive"))
    )
    (net (code "46") (name "M21_") (class "Default")
      (node (ref "C222") (pin "1") (pinfunction "1_1") (pintype "passive"))
      (node (ref "JP128") (pin "3") (pinfunction "3_3") (pintype "passive"))
      (node (ref "R222") (pin "2") (pinfunction "2_2") (pintype "passive"))
    )
    (net (code "47") (name "M22") (class "Default")
      (node (ref "JP101") (pin "7") (pinfunction "7_7") (pintype "passive"))
      (node (ref "R223") (pin "1") (pinfunction "1_1") (pintype "passive"))
    )
    (net (code "48") (name "M22_") (class "Default")
      (node (ref "C223") (pin "1") (pinfunction "1_1") (pintype "passive"))
      (node (ref "JP129") (pin "3") (pinfunction "3_3") (pintype "passive"))
      (node (ref "R223") (pin "2") (pinfunction "2_2") (pintype "passive"))
    )
    (net (code "49") (name "M23") (class "Default")
      (node (ref "JP101") (pin "8") (pinfunction "8_8") (pintype "passive"))
      (node (ref "R224") (pin "1") (pinfunction "1_1") (pintype "passive"))
    )
    (net (code "50") (name "M23_") (class "Default")
      (node (ref "C224") (pin "1") (pinfunction "1_1") (pintype "passive"))
      (node (ref "JP130") (pin "3") (pinfunction "3_3") (pintype "passive"))
      (node (ref "R224") (pin "2") (pinfunction "2_2") (pintype "passive"))
    )
    (net (code "51") (name "M24") (class "Default")
      (node (ref "JP101") (pin "9") (pinfunction "9_9") (pintype "passive"))
      (node (ref "R225") (pin "1") (pinfunction "1_1") (pintype "passive"))
    )
    (net (code "52") (name "M24_") (class "Default")
      (node (ref "C225") (pin "1") (pinfunction "1_1") (pintype "passive"))
      (node (ref "JP131") (pin "3") (pinfunction "3_3") (pintype "passive"))
      (node (ref "R225") (pin "2") (pinfunction "2_2") (pintype "passive"))
    )
    (net (code "53") (name "M25") (class "Default")
      (node (ref "JP101") (pin "10") (pinfunction "10_10") (pintype "passive"))
      (node (ref "R226") (pin "1") (pinfunction "1_1") (pintype "passive"))
    )
    (net (code "54") (name "M25_") (class "Default")
      (node (ref "C226") (pin "1") (pinfunction "1_1") (pintype "passive"))
      (node (ref "JP132") (pin "3") (pinfunction "3_3") (pintype "passive"))
      (node (ref "R226") (pin "2") (pinfunction "2_2") (pintype "passive"))
    )
    (net (code "55") (name "M26") (class "Default")
      (node (ref "JP101") (pin "11") (pinfunction "11_11") (pintype "passive"))
      (node (ref "R227") (pin "1") (pinfunction "1_1") (pintype "passive"))
    )
    (net (code "56") (name "M26_") (class "Default")
      (node (ref "C227") (pin "1") (pinfunction "1_1") (pintype "passive"))
      (node (ref "JP133") (pin "3") (pinfunction "3_3") (pintype "passive"))
      (node (ref "R227") (pin "2") (pinfunction "2_2") (pintype "passive"))
    )
    (net (code "57") (name "M27") (class "Default")
      (node (ref "JP101") (pin "12") (pinfunction "12_12") (pintype "passive"))
      (node (ref "R228") (pin "1") (pinfunction "1_1") (pintype "passive"))
    )
    (net (code "58") (name "M27_") (class "Default")
      (node (ref "C228") (pin "1") (pinfunction "1_1") (pintype "passive"))
      (node (ref "JP134") (pin "3") (pinfunction "3_3") (pintype "passive"))
      (node (ref "R228") (pin "2") (pinfunction "2_2") (pintype "passive"))
    )
    (net (code "59") (name "M28") (class "Default")
      (node (ref "JP101") (pin "13") (pinfunction "13_13") (pintype "passive"))
      (node (ref "R229") (pin "1") (pinfunction "1_1") (pintype "passive"))
    )
    (net (code "60") (name "M28_") (class "Default")
      (node (ref "C229") (pin "1") (pinfunction "1_1") (pintype "passive"))
      (node (ref "JP135") (pin "3") (pinfunction "3_3") (pintype "passive"))
      (node (ref "R229") (pin "2") (pinfunction "2_2") (pintype "passive"))
    )
    (net (code "61") (name "M29") (class "Default")
      (node (ref "JP101") (pin "14") (pinfunction "14_14") (pintype "passive"))
      (node (ref "R230") (pin "1") (pinfunction "1_1") (pintype "passive"))
    )
    (net (code "62") (name "M29_") (class "Default")
      (node (ref "C230") (pin "1") (pinfunction "1_1") (pintype "passive"))
      (node (ref "JP136") (pin "3") (pinfunction "3_3") (pintype "passive"))
      (node (ref "R230") (pin "2") (pinfunction "2_2") (pintype "passive"))
    )
    (net (code "63") (name "M30") (class "Default")
      (node (ref "JP101") (pin "15") (pinfunction "15_15") (pintype "passive"))
      (node (ref "R231") (pin "1") (pinfunction "1_1") (pintype "passive"))
    )
    (net (code "64") (name "M30_") (class "Default")
      (node (ref "C231") (pin "1") (pinfunction "1_1") (pintype "passive"))
      (node (ref "JP137") (pin "3") (pinfunction "3_3") (pintype "passive"))
      (node (ref "R231") (pin "2") (pinfunction "2_2") (pintype "passive"))
    )
    (net (code "65") (name "M31") (class "Default")
      (node (ref "JP101") (pin "16") (pinfunction "16_16") (pintype "passive"))
      (node (ref "R232") (pin "1") (pinfunction "1_1") (pintype "passive"))
    )
    (net (code "66") (name "M31_") (class "Default")
      (node (ref "C232") (pin "1") (pinfunction "1_1") (pintype "passive"))
      (node (ref "JP138") (pin "3") (pinfunction "3_3") (pintype "passive"))
      (node (ref "R232") (pin "2") (pinfunction "2_2") (pintype "passive"))
    )
  )
)
